# M627A.net
KiCad netlist of a schematic drawn in EAGLE
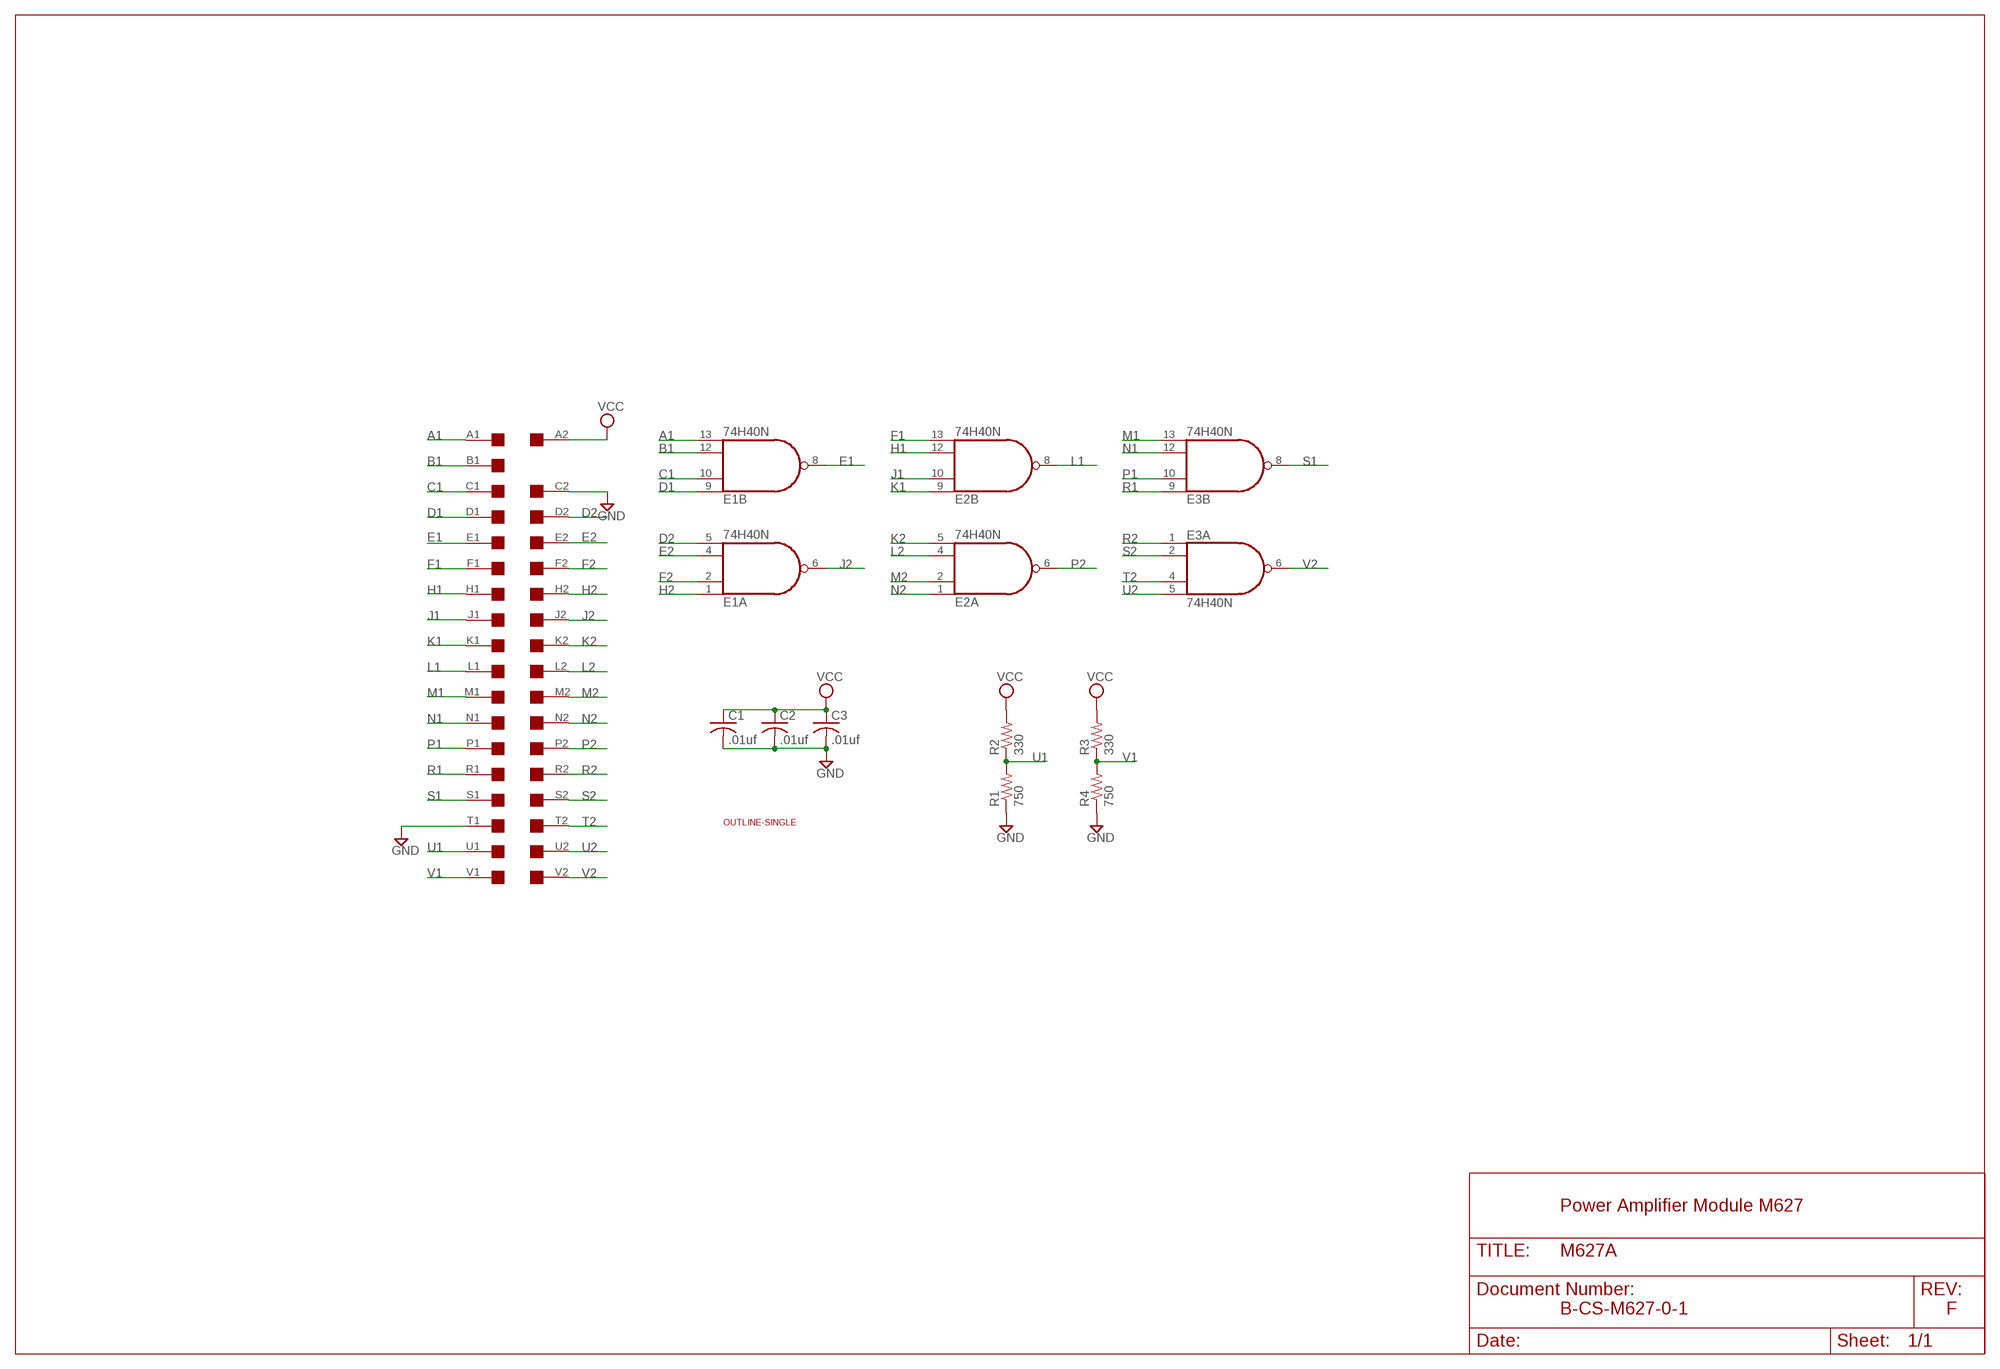
[diagram p0: schematic, sheet 1]

(export (version "E")
  (design (tool "Eeschema 10.0.6"))
  (components
    (comp (ref "C1")
      (value ".01uf")
      (footprint "eagle-import:C050-025X075")
      (libsource (lib "eagle-import") (part "C-US050-025X075"))
    )
    (comp (ref "C2")
      (value ".01uf")
      (footprint "eagle-import:C050-025X075")
      (libsource (lib "eagle-import") (part "C-US050-025X075"))
    )
    (comp (ref "C3")
      (value ".01uf")
      (footprint "eagle-import:C050-025X075")
      (libsource (lib "eagle-import") (part "C-US050-025X075"))
    )
    (comp (ref "E1")
      (value "74H40N")
      (footprint "eagle-import:DIL14")
      (libsource (lib "eagle-import") (part "7420NS"))
    )
    (comp (ref "E2")
      (value "74H40N")
      (footprint "eagle-import:DIL14")
      (libsource (lib "eagle-import") (part "7420NS"))
    )
    (comp (ref "E3")
      (value "74H40N")
      (footprint "eagle-import:DIL14")
      (libsource (lib "eagle-import") (part "7420NS"))
    )
    (comp (ref "R1")
      (value "750")
      (footprint "eagle-import:0207_10")
      (libsource (lib "eagle-import") (part "R-US_0207/10"))
    )
    (comp (ref "R2")
      (value "330")
      (footprint "eagle-import:0207_10")
      (libsource (lib "eagle-import") (part "R-US_0207/10"))
    )
    (comp (ref "R3")
      (value "330")
      (footprint "eagle-import:0207_10")
      (libsource (lib "eagle-import") (part "R-US_0207/10"))
    )
    (comp (ref "R4")
      (value "750")
      (footprint "eagle-import:0207_10")
      (libsource (lib "eagle-import") (part "R-US_0207/10"))
    )
    (comp (ref "U$1")
      (value "OUTLINE-SINGLE")
      (footprint "eagle-import:SINGLE")
      (libsource (lib "eagle-import") (part "OUTLINE-SINGLE"))
    )
    (comp (ref "U$2")
      (value "SINGLE")
      (footprint "eagle-import:EDGE-CON2")
      (libsource (lib "eagle-import") (part "SINGLE"))
    )
  )
  (nets
    (net (code "1") (name "/A1") (class "Default")
      (node (ref "E1") (pin "13") (pinfunction "I3_13") (pintype "input"))
      (node (ref "U$2") (pin "A1") (pinfunction "1_A1") (pintype "bidirectional"))
    )
    (net (code "2") (name "/B1") (class "Default")
      (node (ref "E1") (pin "12") (pinfunction "I2_12") (pintype "input"))
      (node (ref "U$2") (pin "B1") (pinfunction "1_B1") (pintype "bidirectional"))
    )
    (net (code "3") (name "/C1") (class "Default")
      (node (ref "E1") (pin "10") (pinfunction "I1_10") (pintype "input"))
      (node (ref "U$2") (pin "C1") (pinfunction "1_C1") (pintype "bidirectional"))
    )
    (net (code "4") (name "/D1") (class "Default")
      (node (ref "E1") (pin "9") (pinfunction "I0_9") (pintype "input"))
      (node (ref "U$2") (pin "D1") (pinfunction "1_D1") (pintype "bidirectional"))
    )
    (net (code "5") (name "/D2") (class "Default")
      (node (ref "E1") (pin "5") (pinfunction "I3_5") (pintype "input"))
      (node (ref "U$2") (pin "D2") (pinfunction "1_D2") (pintype "bidirectional"))
    )
    (net (code "6") (name "/E1") (class "Default")
      (node (ref "E1") (pin "8") (pinfunction "O_8") (pintype "output"))
      (node (ref "U$2") (pin "E1") (pinfunction "1_E1") (pintype "bidirectional"))
    )
    (net (code "7") (name "/E2") (class "Default")
      (node (ref "E1") (pin "4") (pinfunction "I2_4") (pintype "input"))
      (node (ref "U$2") (pin "E2") (pinfunction "1_E2") (pintype "bidirectional"))
    )
    (net (code "8") (name "/F1") (class "Default")
      (node (ref "E2") (pin "13") (pinfunction "I3_13") (pintype "input"))
      (node (ref "U$2") (pin "F1") (pinfunction "1_F1") (pintype "bidirectional"))
    )
    (net (code "9") (name "/F2") (class "Default")
      (node (ref "E1") (pin "2") (pinfunction "I1_2") (pintype "input"))
      (node (ref "U$2") (pin "F2") (pinfunction "1_F2") (pintype "bidirectional"))
    )
    (net (code "10") (name "/H1") (class "Default")
      (node (ref "E2") (pin "12") (pinfunction "I2_12") (pintype "input"))
      (node (ref "U$2") (pin "H1") (pinfunction "1_H1") (pintype "bidirectional"))
    )
    (net (code "11") (name "/H2") (class "Default")
      (node (ref "E1") (pin "1") (pinfunction "I0_1") (pintype "input"))
      (node (ref "U$2") (pin "H2") (pinfunction "1_H2") (pintype "bidirectional"))
    )
    (net (code "12") (name "/J1") (class "Default")
      (node (ref "E2") (pin "10") (pinfunction "I1_10") (pintype "input"))
      (node (ref "U$2") (pin "J1") (pinfunction "1_J1") (pintype "bidirectional"))
    )
    (net (code "13") (name "/J2") (class "Default")
      (node (ref "E1") (pin "6") (pinfunction "O_6") (pintype "output"))
      (node (ref "U$2") (pin "J2") (pinfunction "1_J2") (pintype "bidirectional"))
    )
    (net (code "14") (name "/K1") (class "Default")
      (node (ref "E2") (pin "9") (pinfunction "I0_9") (pintype "input"))
      (node (ref "U$2") (pin "K1") (pinfunction "1_K1") (pintype "bidirectional"))
    )
    (net (code "15") (name "/K2") (class "Default")
      (node (ref "E2") (pin "5") (pinfunction "I3_5") (pintype "input"))
      (node (ref "U$2") (pin "K2") (pinfunction "1_K2") (pintype "bidirectional"))
    )
    (net (code "16") (name "/L1") (class "Default")
      (node (ref "E2") (pin "8") (pinfunction "O_8") (pintype "output"))
      (node (ref "U$2") (pin "L1") (pinfunction "1_L1") (pintype "bidirectional"))
    )
    (net (code "17") (name "/L2") (class "Default")
      (node (ref "E2") (pin "4") (pinfunction "I2_4") (pintype "input"))
      (node (ref "U$2") (pin "L2") (pinfunction "1_L2") (pintype "bidirectional"))
    )
    (net (code "18") (name "/M1") (class "Default")
      (node (ref "E3") (pin "13") (pinfunction "I3_13") (pintype "input"))
      (node (ref "U$2") (pin "M1") (pinfunction "1_M1") (pintype "bidirectional"))
    )
    (net (code "19") (name "/M2") (class "Default")
      (node (ref "E2") (pin "2") (pinfunction "I1_2") (pintype "input"))
      (node (ref "U$2") (pin "M2") (pinfunction "1_M2") (pintype "bidirectional"))
    )
    (net (code "20") (name "/N1") (class "Default")
      (node (ref "E3") (pin "12") (pinfunction "I2_12") (pintype "input"))
      (node (ref "U$2") (pin "N1") (pinfunction "1_N1") (pintype "bidirectional"))
    )
    (net (code "21") (name "/N2") (class "Default")
      (node (ref "E2") (pin "1") (pinfunction "I0_1") (pintype "input"))
      (node (ref "U$2") (pin "N2") (pinfunction "1_N2") (pintype "bidirectional"))
    )
    (net (code "22") (name "/P1") (class "Default")
      (node (ref "E3") (pin "10") (pinfunction "I1_10") (pintype "input"))
      (node (ref "U$2") (pin "P1") (pinfunction "1_P1") (pintype "bidirectional"))
    )
    (net (code "23") (name "/P2") (class "Default")
      (node (ref "E2") (pin "6") (pinfunction "O_6") (pintype "output"))
      (node (ref "U$2") (pin "P2") (pinfunction "1_P2") (pintype "bidirectional"))
    )
    (net (code "24") (name "/R1") (class "Default")
      (node (ref "E3") (pin "9") (pinfunction "I0_9") (pintype "input"))
      (node (ref "U$2") (pin "R1") (pinfunction "1_R1") (pintype "bidirectional"))
    )
    (net (code "25") (name "/R2") (class "Default")
      (node (ref "E3") (pin "1") (pinfunction "I0_1") (pintype "input"))
      (node (ref "U$2") (pin "R2") (pinfunction "1_R2") (pintype "bidirectional"))
    )
    (net (code "26") (name "/S1") (class "Default")
      (node (ref "E3") (pin "8") (pinfunction "O_8") (pintype "output"))
      (node (ref "U$2") (pin "S1") (pinfunction "1_S1") (pintype "bidirectional"))
    )
    (net (code "27") (name "/S2") (class "Default")
      (node (ref "E3") (pin "2") (pinfunction "I1_2") (pintype "input"))
      (node (ref "U$2") (pin "S2") (pinfunction "1_S2") (pintype "bidirectional"))
    )
    (net (code "28") (name "/T2") (class "Default")
      (node (ref "E3") (pin "4") (pinfunction "I2_4") (pintype "input"))
      (node (ref "U$2") (pin "T2") (pinfunction "1_T2") (pintype "bidirectional"))
    )
    (net (code "29") (name "/U1") (class "Default")
      (node (ref "R1") (pin "2") (pinfunction "2_2") (pintype "passive"))
      (node (ref "R2") (pin "1") (pinfunction "1_1") (pintype "passive"))
      (node (ref "U$2") (pin "U1") (pinfunction "1_U1") (pintype "bidirectional"))
    )
    (net (code "30") (name "/U2") (class "Default")
      (node (ref "E3") (pin "5") (pinfunction "I3_5") (pintype "input"))
      (node (ref "U$2") (pin "U2") (pinfunction "1_U2") (pintype "bidirectional"))
    )
    (net (code "31") (name "/V1") (class "Default")
      (node (ref "R3") (pin "1") (pinfunction "1_1") (pintype "passive"))
      (node (ref "R4") (pin "2") (pinfunction "2_2") (pintype "passive"))
      (node (ref "U$2") (pin "V1") (pinfunction "1_V1") (pintype "bidirectional"))
    )
    (net (code "32") (name "/V2") (class "Default")
      (node (ref "E3") (pin "6") (pinfunction "O_6") (pintype "output"))
      (node (ref "U$2") (pin "V2") (pinfunction "1_V2") (pintype "bidirectional"))
    )
    (net (code "33") (name "GND") (class "Default")
      (node (ref "C1") (pin "2") (pinfunction "2_2") (pintype "passive"))
      (node (ref "C2") (pin "2") (pinfunction "2_2") (pintype "passive"))
      (node (ref "C3") (pin "2") (pinfunction "2_2") (pintype "passive"))
      (node (ref "R1") (pin "1") (pinfunction "1_1") (pintype "passive"))
      (node (ref "R4") (pin "1") (pinfunction "1_1") (pintype "passive"))
      (node (ref "U$2") (pin "C2") (pinfunction "1_C2") (pintype "bidirectional"))
      (node (ref "U$2") (pin "T1") (pinfunction "1_T1") (pintype "bidirectional"))
    )
    (net (code "34") (name "VCC") (class "Default")
      (node (ref "C1") (pin "1") (pinfunction "1_1") (pintype "passive"))
      (node (ref "C2") (pin "1") (pinfunction "1_1") (pintype "passive"))
      (node (ref "C3") (pin "1") (pinfunction "1_1") (pintype "passive"))
      (node (ref "R2") (pin "2") (pinfunction "2_2") (pintype "passive"))
      (node (ref "R3") (pin "2") (pinfunction "2_2") (pintype "passive"))
      (node (ref "U$2") (pin "A2") (pinfunction "1_A2") (pintype "bidirectional"))
    )
  )
)
